# Sensing.net
KiCad netlist of a schematic drawn in Altium Designer
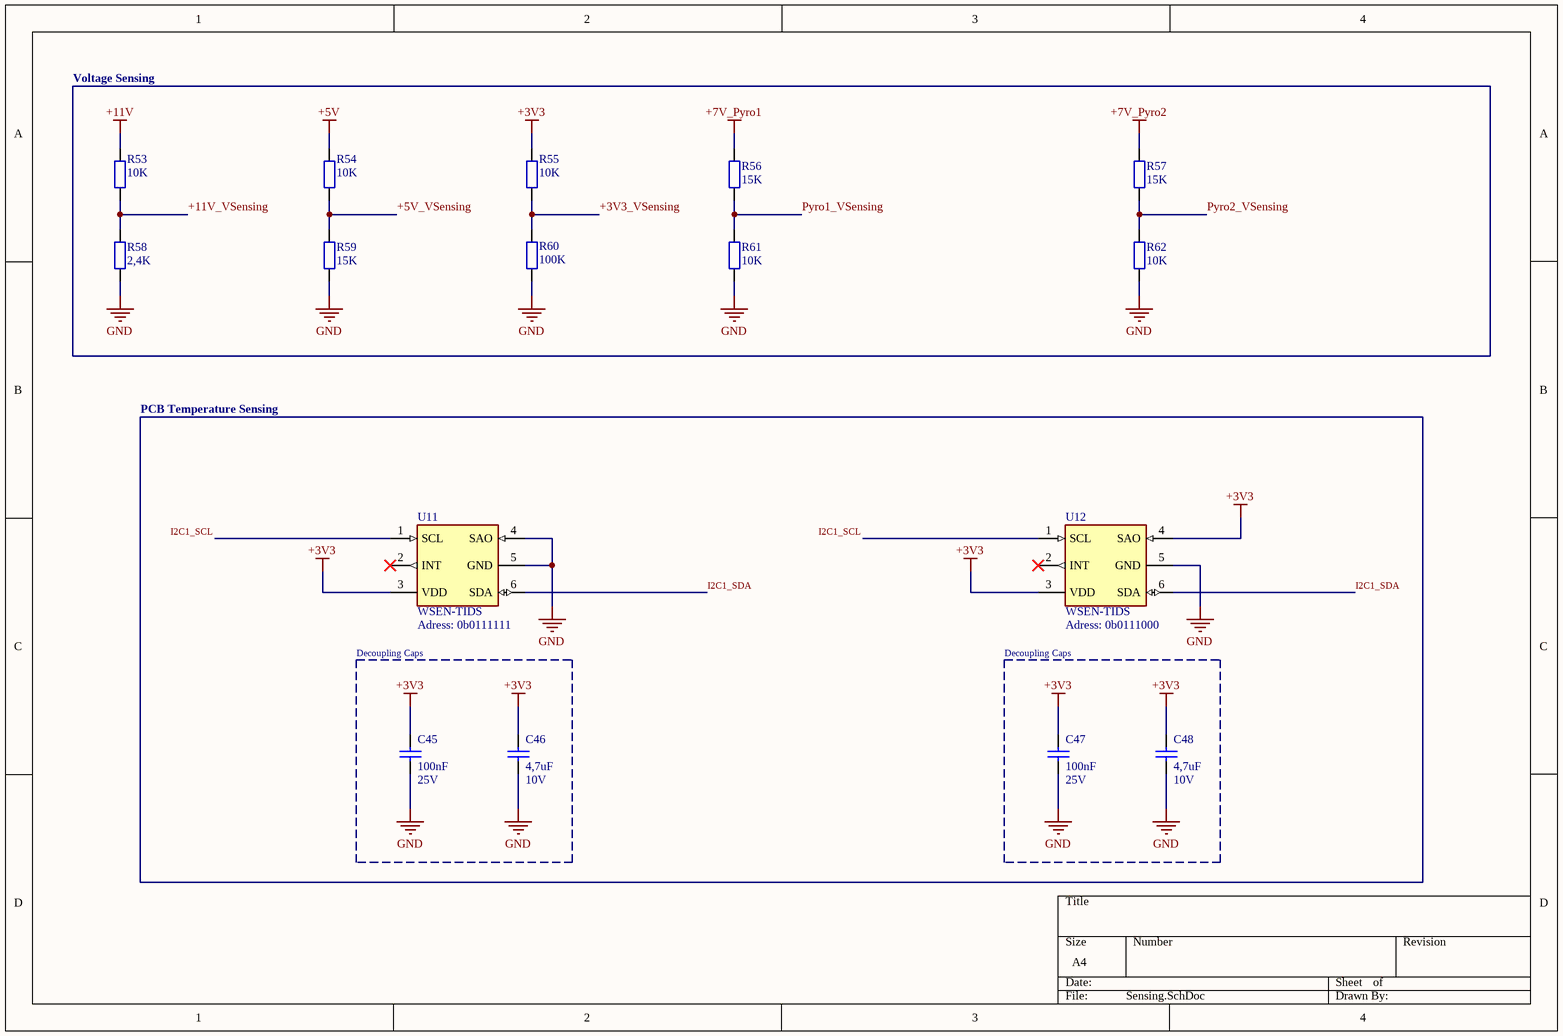
[diagram p0: Sensing.SchDoc]

(export (version "E")
  (design (tool "Eeschema 10.0.6"))
  (components
    (comp (ref "C45")
      (value "100nF")
      (footprint "MY_0603")
      (description "Capacitor, 100nF, 0603, 25V")
      (fields
        (field (name "VOLTAGE") "25V")
        (field (name "MANUFACTURER") "Wurth Elektronik")
        (field (name "MANUFACTURER PART NUMBER") "885012206071")
      )
      (libsource (lib "LEEM UPM") (part "Cap ceramic"))
    )
    (comp (ref "C46")
      (value "4,7uF")
      (footprint "MY_0603")
      (description "Capacitor, 4.7uF, 0603, 10V")
      (fields
        (field (name "VOLTE") "10V")
        (field (name "ASID PART NUMBER") "C-AS")
        (field (name "MANUFACTURER") "Wurth Elektronik")
      )
      (libsource (lib "LEEM UPM") (part "Cap ceramic"))
    )
    (comp (ref "C47")
      (value "100nF")
      (footprint "MY_0603")
      (description "Capacitor, 100nF, 0603, 25V")
      (fields
        (field (name "VOLTAGE") "25V")
        (field (name "MANUFACTURER") "Wurth Elektronik")
        (field (name "MANUFACTURER PART NUMBER") "885012206071")
      )
      (libsource (lib "LEEM UPM") (part "Cap ceramic"))
    )
    (comp (ref "C48")
      (value "4,7uF")
      (footprint "MY_0603")
      (description "Capacitor, 4.7uF, 0603, 10V")
      (fields
        (field (name "VOLTE") "10V")
        (field (name "ASID PART NUMBER") "C-AS")
        (field (name "MANUFACTURER") "Wurth Elektronik")
      )
      (libsource (lib "LEEM UPM") (part "Cap ceramic"))
    )
    (comp (ref "R53")
      (value "10K")
      (footprint "R0603-0.45")
      (description "Resistor, 10K, 0603, 0.1W")
      (fields (field (name "MANUFACTURER") "Wurth") (field (name "MANUFACTURER PART NUMBER") "560112116005"))
      (libsource (lib "IFS_Altium") (part "R"))
    )
    (comp (ref "R54")
      (value "10K")
      (footprint "R0603-0.45")
      (description "Resistor, 10K, 0603, 0.1W")
      (fields (field (name "MANUFACTURER") "Wurth") (field (name "MANUFACTURER PART NUMBER") "560112116005"))
      (libsource (lib "IFS_Altium") (part "R"))
    )
    (comp (ref "R55")
      (value "10K")
      (footprint "R0603-0.45")
      (description "Resistor, 10K, 0603, 0.1W")
      (fields (field (name "MANUFACTURER") "Wurth") (field (name "MANUFACTURER PART NUMBER") "560112116005"))
      (libsource (lib "IFS_Altium") (part "R"))
    )
    (comp (ref "R56")
      (value "15K")
      (footprint "R0603-0.45")
      (description "Resistor, 15K, 0603, 0.1W")
      (fields (field (name "MANUFACTURER") "Wurth") (field (name "MANUFACTURER PART NUMBER") "560112116035"))
      (libsource (lib "LEEM UPM") (part "RK73H2ALTD1004F"))
    )
    (comp (ref "R57")
      (value "15K")
      (footprint "R0603-0.45")
      (description "Resistor, 15K, 0603, 0.1W")
      (fields (field (name "MANUFACTURER") "Wurth") (field (name "MANUFACTURER PART NUMBER") "560112116035"))
      (libsource (lib "LEEM UPM") (part "RK73H2ALTD1004F"))
    )
    (comp (ref "R58")
      (value "2,4K")
      (footprint "R0603-0.45")
      (description "Resistor, 2.4K, 0603, 0.1W")
      (fields (field (name "MANUFACTURER") "Wurth") (field (name "MANUFACTURER PART NUMBER") "560112116061"))
      (libsource (lib "LEEM UPM") (part "RK73H2ALTD1004F"))
    )
    (comp (ref "R59")
      (value "15K")
      (footprint "R0603-0.45")
      (description "Resistor, 15K, 0603, 0.1W")
      (fields (field (name "MANUFACTURER") "Wurth") (field (name "MANUFACTURER PART NUMBER") "560112116035"))
      (libsource (lib "LEEM UPM") (part "RK73H2ALTD1004F"))
    )
    (comp (ref "R60")
      (value "100K")
      (footprint "R0603-0.45")
      (description "Resistor, 100K, 0603, 0.1W")
      (fields (field (name "MANUFACTURER") "Wurth") (field (name "MANUFACTURER PART NUMBER") "560112116004"))
      (libsource (lib "IFS_Altium") (part "R"))
    )
    (comp (ref "R61")
      (value "10K")
      (footprint "R0603-0.45")
      (description "Resistor, 10K, 0603, 0.1W")
      (fields (field (name "MANUFACTURER") "Wurth") (field (name "MANUFACTURER PART NUMBER") "560112116005"))
      (libsource (lib "IFS_Altium") (part "R"))
    )
    (comp (ref "R62")
      (value "10K")
      (footprint "R0603-0.45")
      (description "Resistor, 10K, 0603, 0.1W")
      (fields (field (name "MANUFACTURER") "Wurth") (field (name "MANUFACTURER PART NUMBER") "560112116005"))
      (libsource (lib "IFS_Altium") (part "R"))
    )
    (comp (ref "U11")
      (value "WSEN-TIDS")
      (footprint "WSEN-TIDS-Footprint-1")
      (description "Analog Resistance Temperature Sensor")
      (fields (field (name "MANUFACTURER") "Wurth Elektronik"))
      (libsource (lib "LEEM UPM") (part "WSEN-TIDS"))
    )
    (comp (ref "U12")
      (value "WSEN-TIDS")
      (footprint "WSEN-TIDS-Footprint-1")
      (description "Analog Resistance Temperature Sensor")
      (fields (field (name "MANUFACTURER") "Wurth Elektronik"))
      (libsource (lib "LEEM UPM") (part "WSEN-TIDS"))
    )
  )
  (nets
    (net (code "1") (name "+3V3") (class "Default")
      (node (ref "C45") (pin "2") (pinfunction "2_2") (pintype "passive"))
      (node (ref "C46") (pin "2") (pinfunction "2_2") (pintype "passive"))
      (node (ref "C47") (pin "2") (pinfunction "2_2") (pintype "passive"))
      (node (ref "C48") (pin "2") (pinfunction "2_2") (pintype "passive"))
      (node (ref "R55") (pin "1") (pinfunction "1_1") (pintype "passive"))
      (node (ref "U11") (pin "3") (pinfunction "VDD_3") (pintype "power_in"))
      (node (ref "U12") (pin "3") (pinfunction "VDD_3") (pintype "power_in"))
      (node (ref "U12") (pin "4") (pinfunction "SAO_4") (pintype "input"))
    )
    (net (code "2") (name "+5V") (class "Default")
      (node (ref "R54") (pin "1") (pinfunction "1_1") (pintype "passive"))
    )
    (net (code "3") (name "+7V_Pyro1") (class "Default")
      (node (ref "R56") (pin "2") (pinfunction "2_2") (pintype "passive"))
    )
    (net (code "4") (name "+7V_Pyro2") (class "Default")
      (node (ref "R57") (pin "2") (pinfunction "2_2") (pintype "passive"))
    )
    (net (code "5") (name "+11V") (class "Default")
      (node (ref "R53") (pin "1") (pinfunction "1_1") (pintype "passive"))
    )
    (net (code "6") (name "/+3V3_VSensing") (class "Default")
      (node (ref "R55") (pin "2") (pinfunction "2_2") (pintype "passive"))
      (node (ref "R60") (pin "1") (pinfunction "1_1") (pintype "passive"))
    )
    (net (code "7") (name "/+5V_VSensing") (class "Default")
      (node (ref "R54") (pin "2") (pinfunction "2_2") (pintype "passive"))
      (node (ref "R59") (pin "2") (pinfunction "2_2") (pintype "passive"))
    )
    (net (code "8") (name "/+11V_VSensing") (class "Default")
      (node (ref "R53") (pin "2") (pinfunction "2_2") (pintype "passive"))
      (node (ref "R58") (pin "2") (pinfunction "2_2") (pintype "passive"))
    )
    (net (code "9") (name "/I2C1_SCL") (class "Default")
      (node (ref "U11") (pin "1") (pinfunction "SCL_1") (pintype "input"))
      (node (ref "U12") (pin "1") (pinfunction "SCL_1") (pintype "input"))
    )
    (net (code "10") (name "/I2C1_SDA") (class "Default")
      (node (ref "U11") (pin "6") (pinfunction "SDA_6") (pintype "bidirectional"))
      (node (ref "U12") (pin "6") (pinfunction "SDA_6") (pintype "bidirectional"))
    )
    (net (code "11") (name "/Pyro1_VSensing") (class "Default")
      (node (ref "R56") (pin "1") (pinfunction "1_1") (pintype "passive"))
      (node (ref "R61") (pin "1") (pinfunction "1_1") (pintype "passive"))
    )
    (net (code "12") (name "/Pyro2_VSensing") (class "Default")
      (node (ref "R57") (pin "1") (pinfunction "1_1") (pintype "passive"))
      (node (ref "R62") (pin "1") (pinfunction "1_1") (pintype "passive"))
    )
    (net (code "13") (name "GND") (class "Default")
      (node (ref "C45") (pin "1") (pinfunction "1_1") (pintype "passive"))
      (node (ref "C46") (pin "1") (pinfunction "1_1") (pintype "passive"))
      (node (ref "C47") (pin "1") (pinfunction "1_1") (pintype "passive"))
      (node (ref "C48") (pin "1") (pinfunction "1_1") (pintype "passive"))
      (node (ref "R58") (pin "1") (pinfunction "1_1") (pintype "passive"))
      (node (ref "R59") (pin "1") (pinfunction "1_1") (pintype "passive"))
      (node (ref "R60") (pin "2") (pinfunction "2_2") (pintype "passive"))
      (node (ref "R61") (pin "2") (pinfunction "2_2") (pintype "passive"))
      (node (ref "R62") (pin "2") (pinfunction "2_2") (pintype "passive"))
      (node (ref "U11") (pin "4") (pinfunction "SAO_4") (pintype "input"))
      (node (ref "U11") (pin "5") (pinfunction "GND_5") (pintype "power_in"))
      (node (ref "U12") (pin "5") (pinfunction "GND_5") (pintype "power_in"))
    )
    (net (code "14") (name "unconnected-(U11-INT-Pad2)") (class "Default")
      (node (ref "U11") (pin "2") (pinfunction "INT_2") (pintype "output+no_connect"))
    )
    (net (code "15") (name "unconnected-(U12-INT-Pad2)") (class "Default")
      (node (ref "U12") (pin "2") (pinfunction "INT_2") (pintype "output+no_connect"))
    )
  )
)
